# JOY_1_0.net
KiCad netlist of a schematic drawn in EAGLE
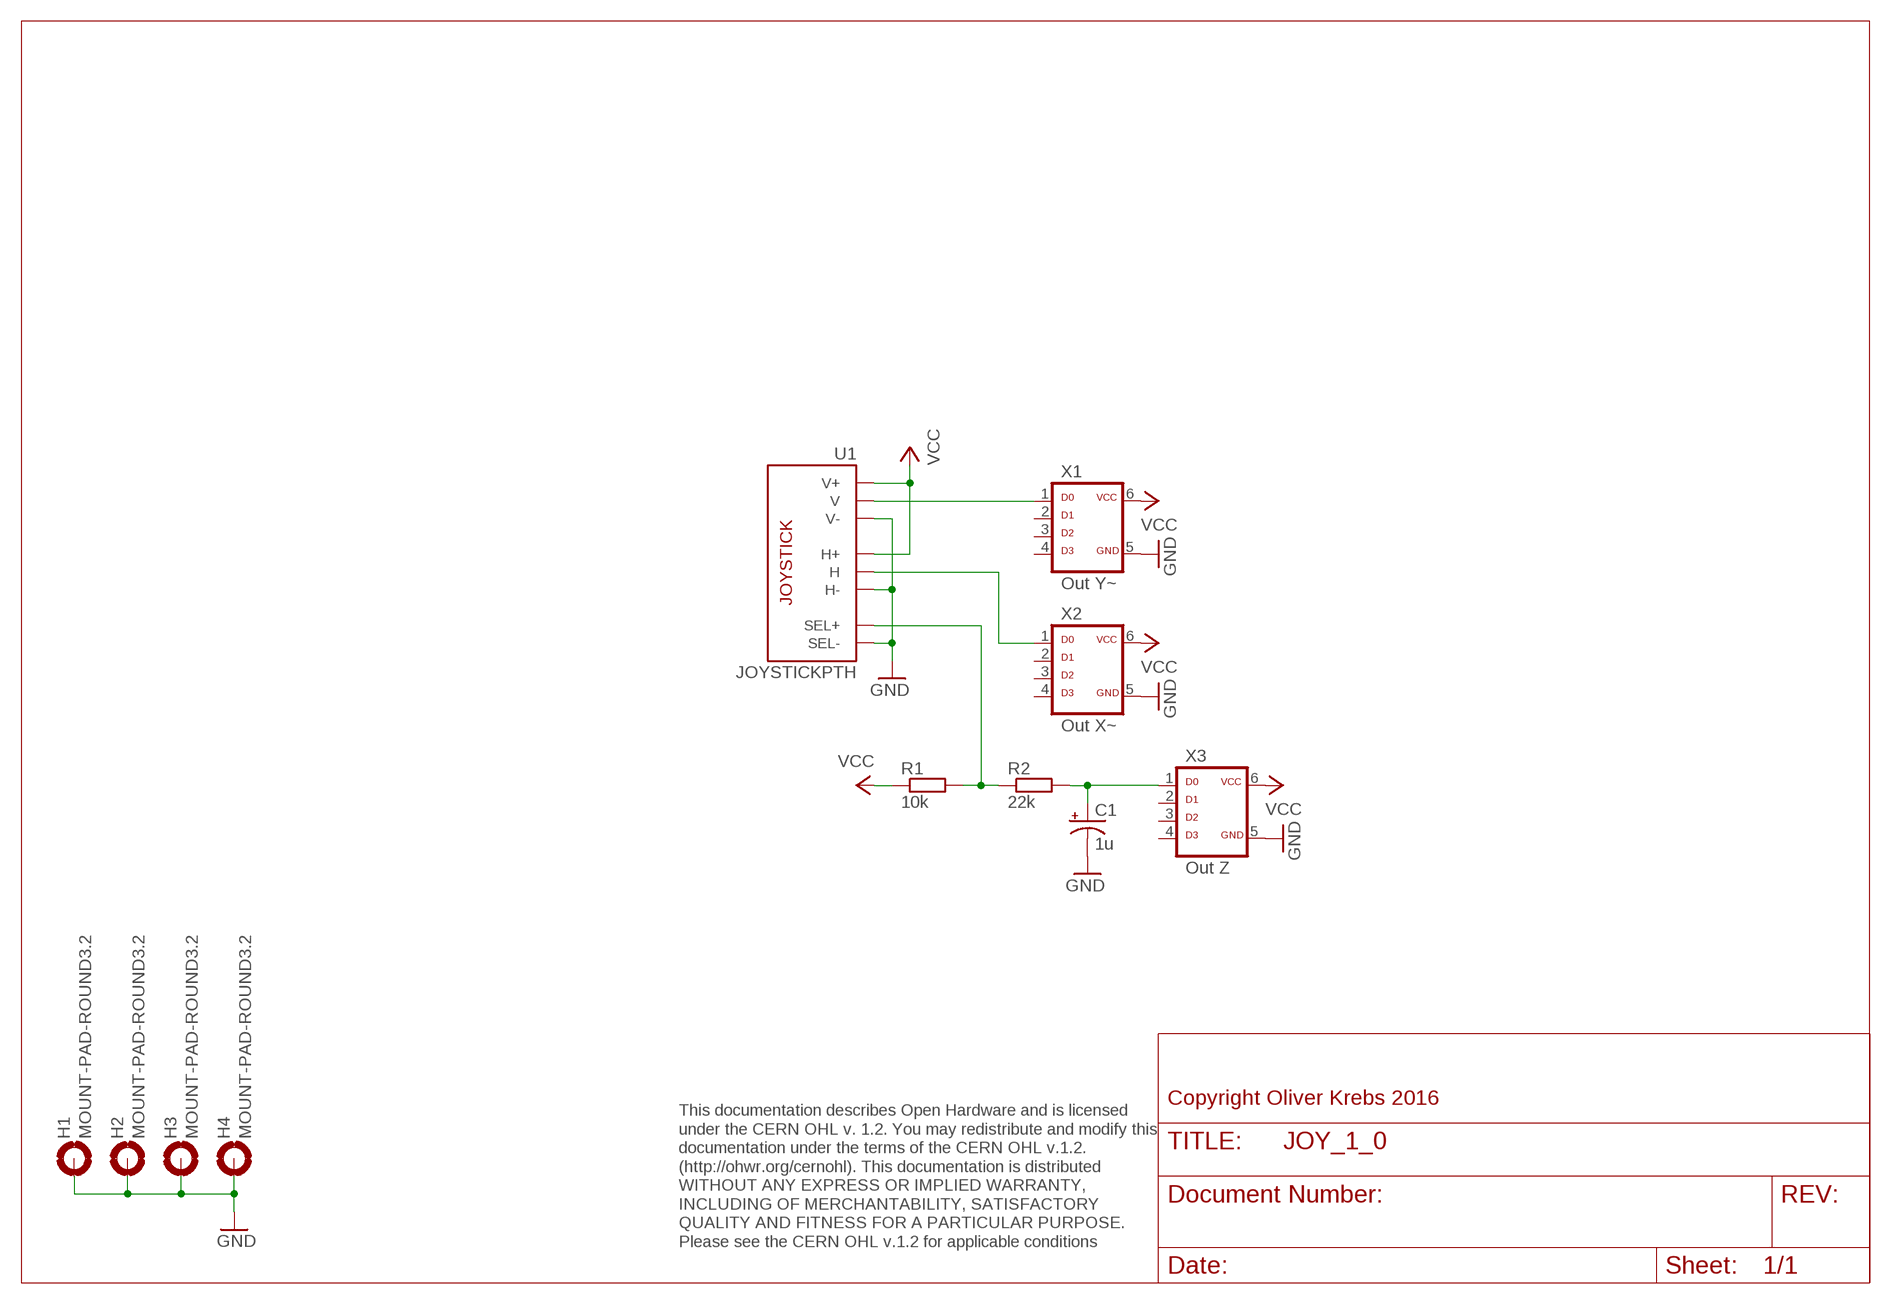
[diagram p0: schematic, sheet 1]

(export (version "E")
  (design (tool "Eeschema 10.0.6"))
  (components
    (comp (ref "C1")
      (value "1u")
      (footprint "eagle-import:CPOL-RADIAL-10UF-25V")
      (libsource (lib "eagle-import") (part "CAP_POLPTH2"))
    )
    (comp (ref "H1")
      (value "MOUNT-PAD-ROUND3.2")
      (footprint "eagle-import:3,2-PAD")
      (libsource (lib "eagle-import") (part "MOUNT-PAD-ROUND3.2"))
    )
    (comp (ref "H2")
      (value "MOUNT-PAD-ROUND3.2")
      (footprint "eagle-import:3,2-PAD")
      (libsource (lib "eagle-import") (part "MOUNT-PAD-ROUND3.2"))
    )
    (comp (ref "H3")
      (value "MOUNT-PAD-ROUND3.2")
      (footprint "eagle-import:3,2-PAD")
      (libsource (lib "eagle-import") (part "MOUNT-PAD-ROUND3.2"))
    )
    (comp (ref "H4")
      (value "MOUNT-PAD-ROUND3.2")
      (footprint "eagle-import:3,2-PAD")
      (libsource (lib "eagle-import") (part "MOUNT-PAD-ROUND3.2"))
    )
    (comp (ref "R1")
      (value "10k")
      (footprint "eagle-import:0207_10")
      (libsource (lib "eagle-import") (part "R-EU_0207/10"))
    )
    (comp (ref "R2")
      (value "22k")
      (footprint "eagle-import:0207_10")
      (libsource (lib "eagle-import") (part "R-EU_0207/10"))
    )
    (comp (ref "U1")
      (value "JOYSTICKPTH")
      (footprint "eagle-import:JOYSTICK")
      (libsource (lib "eagle-import") (part "JOYSTICKPTH"))
    )
    (comp (ref "X1")
      (value "Out Y~")
      (footprint "eagle-import:ML-6")
      (libsource (lib "eagle-import") (part "ML6D"))
    )
    (comp (ref "X2")
      (value "Out X~")
      (footprint "eagle-import:ML-6")
      (libsource (lib "eagle-import") (part "ML6D"))
    )
    (comp (ref "X3")
      (value "Out Z")
      (footprint "eagle-import:ML-6")
      (libsource (lib "eagle-import") (part "ML6D"))
    )
  )
  (nets
    (net (code "1") (name "GND") (class "Default")
      (node (ref "C1") (pin "2") (pinfunction "-_2") (pintype "passive"))
      (node (ref "H1") (pin "B3,2") (pinfunction "MOUNT_B3,2") (pintype "passive"))
      (node (ref "H2") (pin "B3,2") (pinfunction "MOUNT_B3,2") (pintype "passive"))
      (node (ref "H3") (pin "B3,2") (pinfunction "MOUNT_B3,2") (pintype "passive"))
      (node (ref "H4") (pin "B3,2") (pinfunction "MOUNT_B3,2") (pintype "passive"))
      (node (ref "U1") (pin "B2A") (pinfunction "SEL-_B2A") (pintype "bidirectional"))
      (node (ref "U1") (pin "H3") (pinfunction "H-_H3") (pintype "bidirectional"))
      (node (ref "U1") (pin "V3") (pinfunction "V-_V3") (pintype "bidirectional"))
      (node (ref "X1") (pin "5") (pinfunction "5_5") (pintype "passive"))
      (node (ref "X2") (pin "5") (pinfunction "5_5") (pintype "passive"))
      (node (ref "X3") (pin "5") (pinfunction "5_5") (pintype "passive"))
    )
    (net (code "2") (name "Net-(C1-+)") (class "Default")
      (node (ref "C1") (pin "1") (pinfunction "+_1") (pintype "passive"))
      (node (ref "R2") (pin "2") (pinfunction "2_2") (pintype "passive"))
      (node (ref "X3") (pin "1") (pinfunction "1_1") (pintype "passive"))
    )
    (net (code "3") (name "Net-(U1-H)") (class "Default")
      (node (ref "U1") (pin "H2") (pinfunction "H_H2") (pintype "bidirectional"))
      (node (ref "X2") (pin "1") (pinfunction "1_1") (pintype "passive"))
    )
    (net (code "4") (name "Net-(U1-SEL+)") (class "Default")
      (node (ref "R1") (pin "2") (pinfunction "2_2") (pintype "passive"))
      (node (ref "R2") (pin "1") (pinfunction "1_1") (pintype "passive"))
      (node (ref "U1") (pin "B1A") (pinfunction "SEL+_B1A") (pintype "bidirectional"))
    )
    (net (code "5") (name "Net-(U1-V)") (class "Default")
      (node (ref "U1") (pin "V2") (pinfunction "V_V2") (pintype "bidirectional"))
      (node (ref "X1") (pin "1") (pinfunction "1_1") (pintype "passive"))
    )
    (net (code "6") (name "VCC") (class "Default")
      (node (ref "R1") (pin "1") (pinfunction "1_1") (pintype "passive"))
      (node (ref "U1") (pin "H1") (pinfunction "H+_H1") (pintype "bidirectional"))
      (node (ref "U1") (pin "V1") (pinfunction "V+_V1") (pintype "bidirectional"))
      (node (ref "X1") (pin "6") (pinfunction "6_6") (pintype "passive"))
      (node (ref "X2") (pin "6") (pinfunction "6_6") (pintype "passive"))
      (node (ref "X3") (pin "6") (pinfunction "6_6") (pintype "passive"))
    )
    (net (code "7") (name "unconnected-(X1-Pad2)") (class "Default")
      (node (ref "X1") (pin "2") (pinfunction "2_2") (pintype "passive"))
    )
    (net (code "8") (name "unconnected-(X1-Pad3)") (class "Default")
      (node (ref "X1") (pin "3") (pinfunction "3_3") (pintype "passive"))
    )
    (net (code "9") (name "unconnected-(X1-Pad4)") (class "Default")
      (node (ref "X1") (pin "4") (pinfunction "4_4") (pintype "passive"))
    )
    (net (code "10") (name "unconnected-(X2-Pad2)") (class "Default")
      (node (ref "X2") (pin "2") (pinfunction "2_2") (pintype "passive"))
    )
    (net (code "11") (name "unconnected-(X2-Pad3)") (class "Default")
      (node (ref "X2") (pin "3") (pinfunction "3_3") (pintype "passive"))
    )
    (net (code "12") (name "unconnected-(X2-Pad4)") (class "Default")
      (node (ref "X2") (pin "4") (pinfunction "4_4") (pintype "passive"))
    )
    (net (code "13") (name "unconnected-(X3-Pad2)") (class "Default")
      (node (ref "X3") (pin "2") (pinfunction "2_2") (pintype "passive"))
    )
    (net (code "14") (name "unconnected-(X3-Pad3)") (class "Default")
      (node (ref "X3") (pin "3") (pinfunction "3_3") (pintype "passive"))
    )
    (net (code "15") (name "unconnected-(X3-Pad4)") (class "Default")
      (node (ref "X3") (pin "4") (pinfunction "4_4") (pintype "passive"))
    )
  )
)
